# speed_truck.net
KiCad netlist of a schematic drawn in EasyEDA
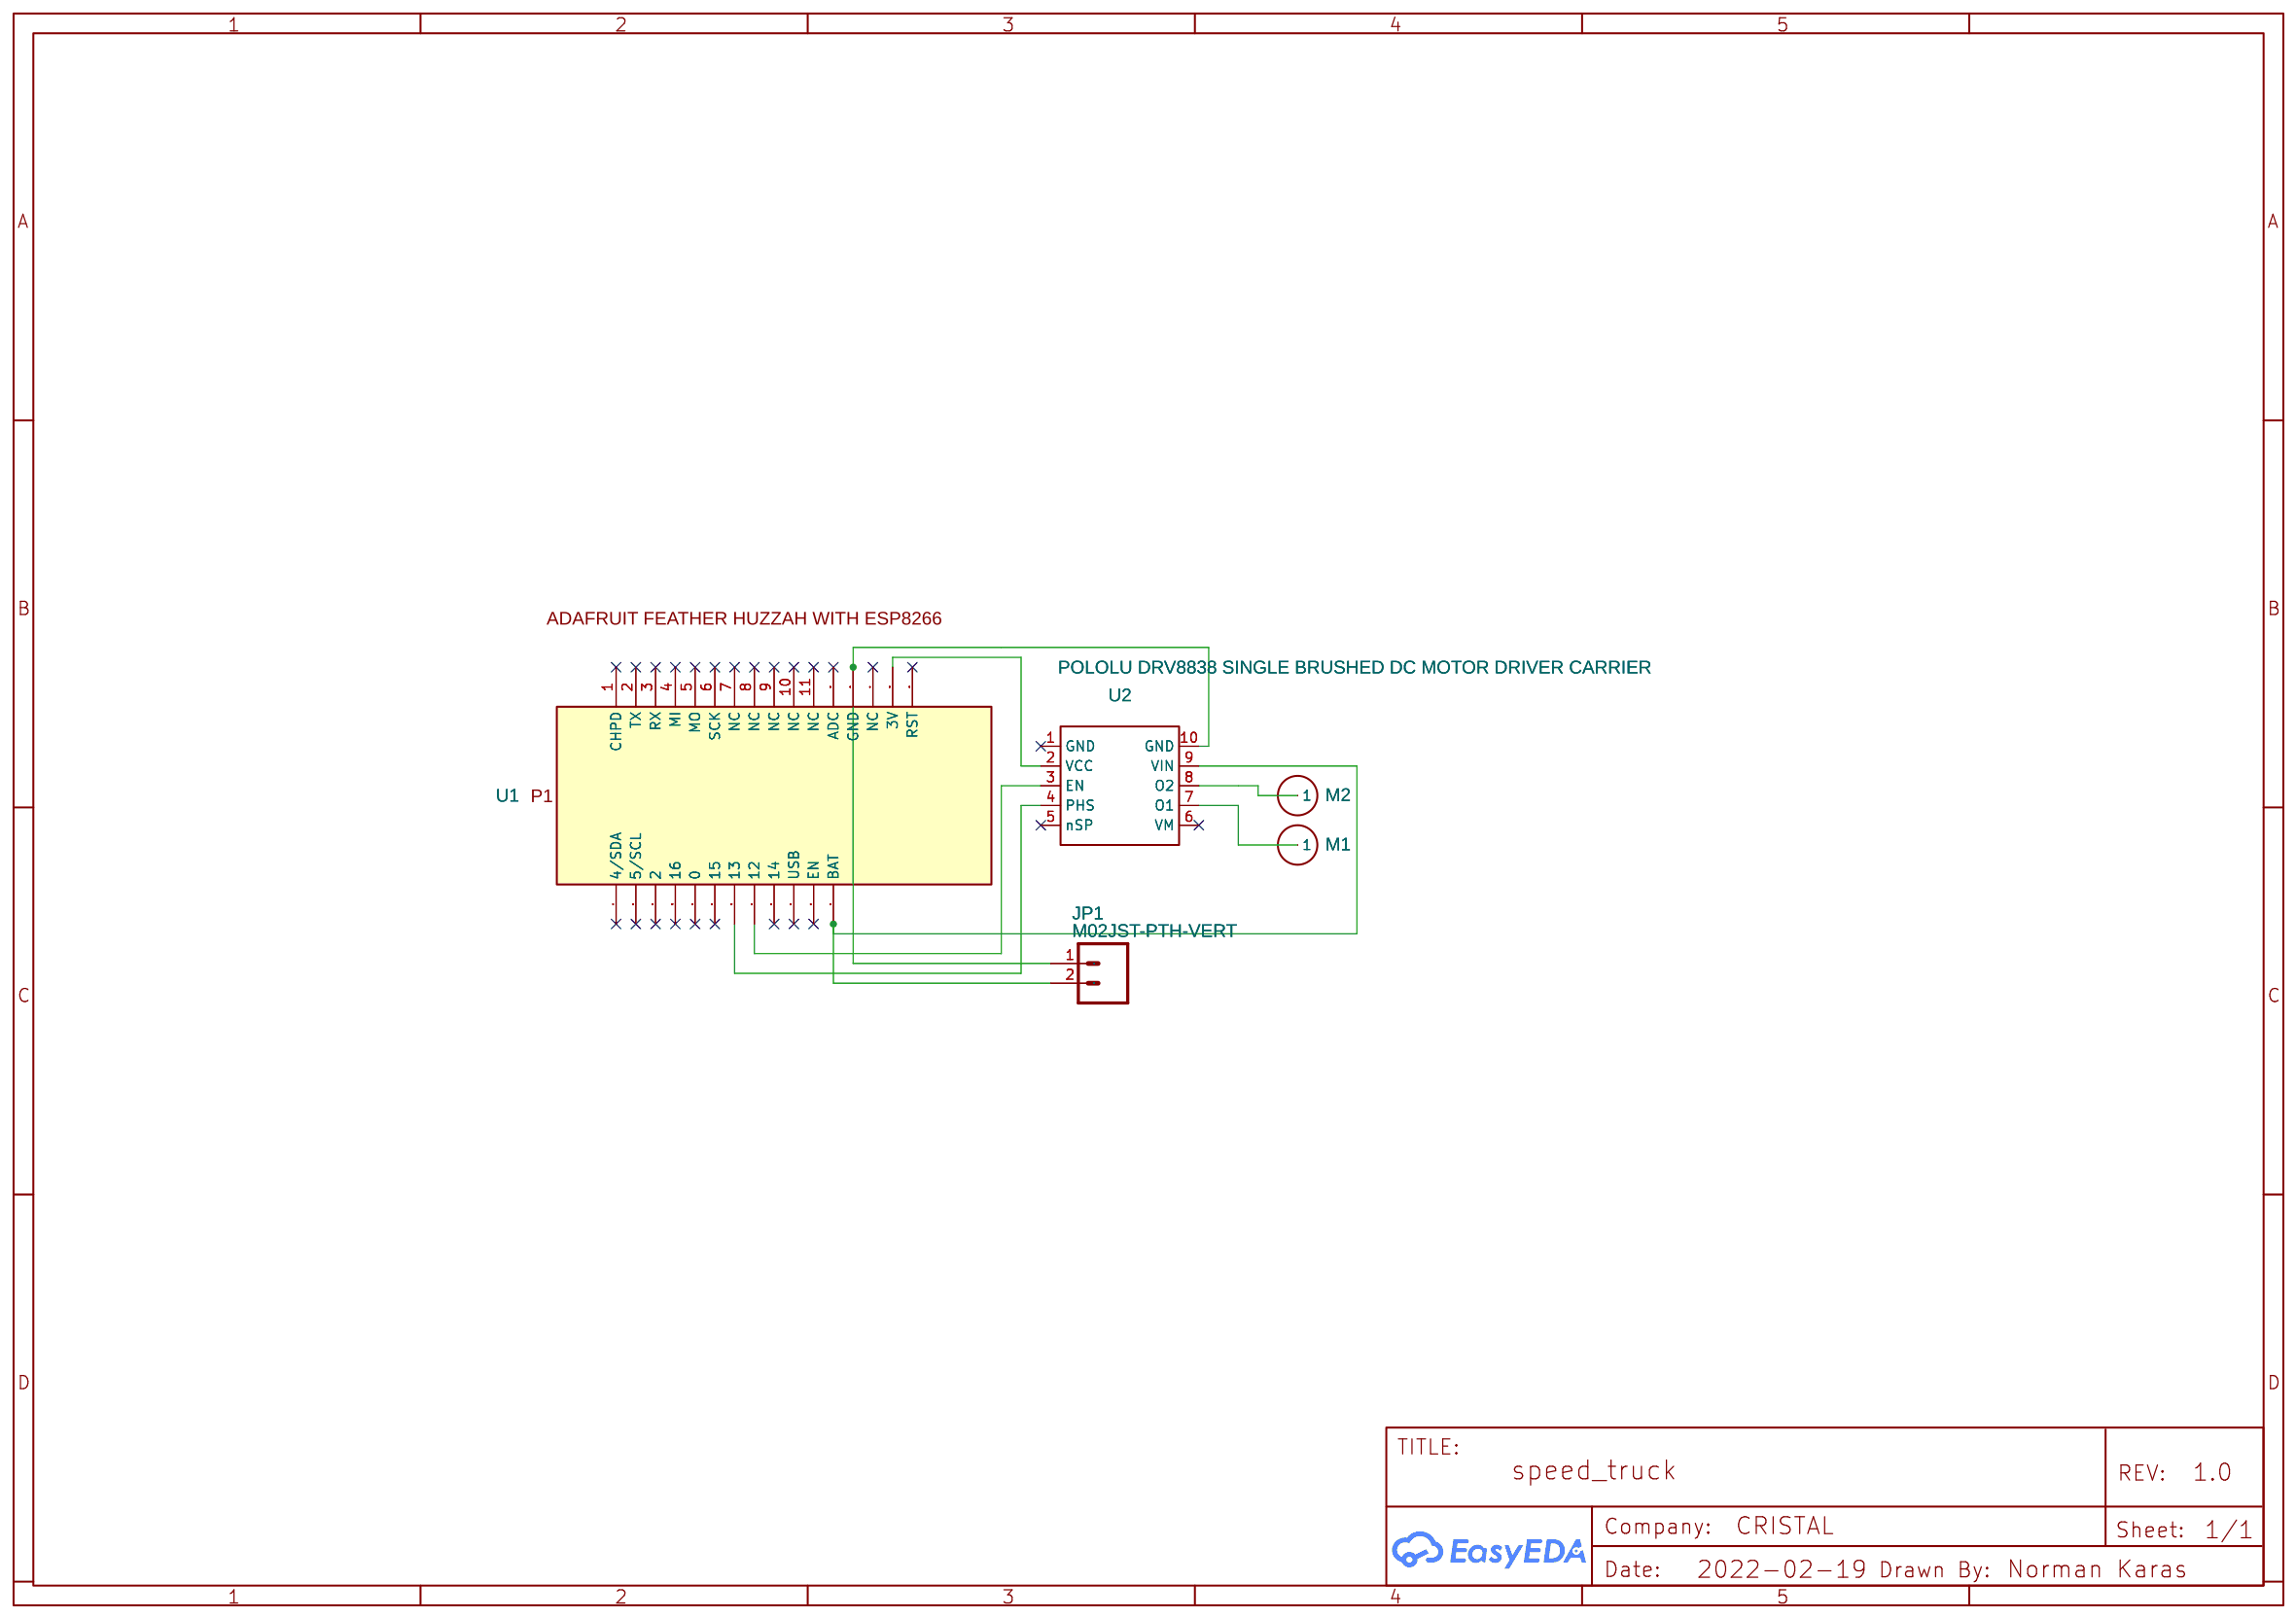
[diagram p0: schematic sheet]

(export (version "E")
  (design (tool "Eeschema 10.0.6"))
  (components
    (comp (ref "JP1") (value "M02JST-PTH-VERT") (libsource (lib "") (part "M02JST-PTH-VERT")))
    (comp (ref "M1")
      (value "Pad through hole 0.5mm hole 1mm pad")
      (libsource (lib "") (part "Pad through hole 0.5mm hole 1mm pad"))
    )
    (comp (ref "M2")
      (value "Pad through hole 0.5mm hole 1mm pad")
      (libsource (lib "") (part "Pad through hole 0.5mm hole 1mm pad"))
    )
    (comp (ref "U1")
      (value "Adafruit Huzzah ESP8266 - K5MAP")
      (libsource (lib "") (part "Adafruit Huzzah ESP8266 - K5MAP"))
    )
    (comp (ref "U2")
      (value "POLOLU DRV8838 SINGLE BRUSHED DC MOTOR DRIVER CARRIER")
      (fields (field (name "BOM_Manufacturer Part") "https://www.pololu.com/product/2990"))
      (libsource (lib "") (part "POLOLU DRV8838 SINGLE BRUSHED DC MOTOR DRIVER CARRIER"))
    )
  )
  (nets
    (net (code "1") (name "Net-(U1-3V)") (class "Default")
      (node (ref "U1") (pin "15") (pinfunction "3V_15") (pintype "unspecified"))
      (node (ref "U2") (pin "2") (pinfunction "VCC_2") (pintype "unspecified"))
    )
    (net (code "2") (name "Net-(U1-12)") (class "Default")
      (node (ref "U1") (pin "24") (pinfunction "12_24") (pintype "unspecified"))
      (node (ref "U2") (pin "3") (pinfunction "EN_3") (pintype "unspecified"))
    )
    (net (code "3") (name "Net-(U1-13)") (class "Default")
      (node (ref "U1") (pin "23") (pinfunction "13_23") (pintype "unspecified"))
      (node (ref "U2") (pin "4") (pinfunction "PHS_4") (pintype "unspecified"))
    )
    (net (code "4") (name "Net-(U1-BAT)") (class "Default")
      (node (ref "JP1") (pin "2") (pinfunction "2_2") (pintype "bidirectional"))
      (node (ref "U1") (pin "28") (pinfunction "BAT_28") (pintype "unspecified"))
      (node (ref "U2") (pin "9") (pinfunction "VIN_9") (pintype "unspecified"))
    )
    (net (code "5") (name "Net-(U1-GND)") (class "Default")
      (node (ref "JP1") (pin "1") (pinfunction "1_1") (pintype "bidirectional"))
      (node (ref "U1") (pin "13") (pinfunction "GND_13") (pintype "unspecified"))
      (node (ref "U2") (pin "10") (pinfunction "GND_10") (pintype "unspecified"))
    )
    (net (code "6") (name "Net-(U2-O1)") (class "Default")
      (node (ref "M1") (pin "1") (pinfunction "1_1") (pintype "unspecified"))
      (node (ref "U2") (pin "7") (pinfunction "O1_7") (pintype "unspecified"))
    )
    (net (code "7") (name "Net-(U2-O2)") (class "Default")
      (node (ref "M2") (pin "1") (pinfunction "1_1") (pintype "unspecified"))
      (node (ref "U2") (pin "8") (pinfunction "O2_8") (pintype "unspecified"))
    )
    (net (code "8") (name "unconnected-(U1-0-Pad21)") (class "Default")
      (node (ref "U1") (pin "21") (pinfunction "0_21") (pintype "unspecified+no_connect"))
    )
    (net (code "9") (name "unconnected-(U1-2-Pad19)") (class "Default")
      (node (ref "U1") (pin "19") (pinfunction "2_19") (pintype "unspecified+no_connect"))
    )
    (net (code "10") (name "unconnected-(U1-4{slash}SDA-Pad17)") (class "Default")
      (node (ref "U1") (pin "17") (pinfunction "4/SDA_17") (pintype "unspecified+no_connect"))
    )
    (net (code "11") (name "unconnected-(U1-5{slash}SCL-Pad18)") (class "Default")
      (node (ref "U1") (pin "18") (pinfunction "5/SCL_18") (pintype "unspecified+no_connect"))
    )
    (net (code "12") (name "unconnected-(U1-14-Pad25)") (class "Default")
      (node (ref "U1") (pin "25") (pinfunction "14_25") (pintype "unspecified+no_connect"))
    )
    (net (code "13") (name "unconnected-(U1-15-Pad22)") (class "Default")
      (node (ref "U1") (pin "22") (pinfunction "15_22") (pintype "unspecified+no_connect"))
    )
    (net (code "14") (name "unconnected-(U1-16-Pad20)") (class "Default")
      (node (ref "U1") (pin "20") (pinfunction "16_20") (pintype "unspecified+no_connect"))
    )
    (net (code "15") (name "unconnected-(U1-ADC-Pad12)") (class "Default")
      (node (ref "U1") (pin "12") (pinfunction "ADC_12") (pintype "unspecified+no_connect"))
    )
    (net (code "16") (name "unconnected-(U1-CHPD-Pad1)") (class "Default")
      (node (ref "U1") (pin "1") (pinfunction "CHPD_1") (pintype "unspecified+no_connect"))
    )
    (net (code "17") (name "unconnected-(U1-EN-Pad27)") (class "Default")
      (node (ref "U1") (pin "27") (pinfunction "EN_27") (pintype "unspecified+no_connect"))
    )
    (net (code "18") (name "unconnected-(U1-MI-Pad4)") (class "Default")
      (node (ref "U1") (pin "4") (pinfunction "MI_4") (pintype "unspecified+no_connect"))
    )
    (net (code "19") (name "unconnected-(U1-MO-Pad5)") (class "Default")
      (node (ref "U1") (pin "5") (pinfunction "MO_5") (pintype "unspecified+no_connect"))
    )
    (net (code "20") (name "unconnected-(U1-NC-Pad7)") (class "Default")
      (node (ref "U1") (pin "7") (pinfunction "NC_7") (pintype "unspecified+no_connect"))
    )
    (net (code "21") (name "unconnected-(U1-NC-Pad8)") (class "Default")
      (node (ref "U1") (pin "8") (pinfunction "NC_8") (pintype "unspecified+no_connect"))
    )
    (net (code "22") (name "unconnected-(U1-NC-Pad9)") (class "Default")
      (node (ref "U1") (pin "9") (pinfunction "NC_9") (pintype "unspecified+no_connect"))
    )
    (net (code "23") (name "unconnected-(U1-NC-Pad10)") (class "Default")
      (node (ref "U1") (pin "10") (pinfunction "NC_10") (pintype "unspecified+no_connect"))
    )
    (net (code "24") (name "unconnected-(U1-NC-Pad11)") (class "Default")
      (node (ref "U1") (pin "11") (pinfunction "NC_11") (pintype "unspecified+no_connect"))
    )
    (net (code "25") (name "unconnected-(U1-NC-Pad14)") (class "Default")
      (node (ref "U1") (pin "14") (pinfunction "NC_14") (pintype "unspecified+no_connect"))
    )
    (net (code "26") (name "unconnected-(U1-RST-Pad16)") (class "Default")
      (node (ref "U1") (pin "16") (pinfunction "RST_16") (pintype "unspecified+no_connect"))
    )
    (net (code "27") (name "unconnected-(U1-RX-Pad3)") (class "Default")
      (node (ref "U1") (pin "3") (pinfunction "RX_3") (pintype "unspecified+no_connect"))
    )
    (net (code "28") (name "unconnected-(U1-SCK-Pad6)") (class "Default")
      (node (ref "U1") (pin "6") (pinfunction "SCK_6") (pintype "unspecified+no_connect"))
    )
    (net (code "29") (name "unconnected-(U1-TX-Pad2)") (class "Default")
      (node (ref "U1") (pin "2") (pinfunction "TX_2") (pintype "unspecified+no_connect"))
    )
    (net (code "30") (name "unconnected-(U1-USB-Pad26)") (class "Default")
      (node (ref "U1") (pin "26") (pinfunction "USB_26") (pintype "unspecified+no_connect"))
    )
    (net (code "31") (name "unconnected-(U2-GND-Pad1)") (class "Default")
      (node (ref "U2") (pin "1") (pinfunction "GND_1") (pintype "unspecified+no_connect"))
    )
    (net (code "32") (name "unconnected-(U2-VM-Pad6)") (class "Default")
      (node (ref "U2") (pin "6") (pinfunction "VM_6") (pintype "unspecified+no_connect"))
    )
    (net (code "33") (name "unconnected-(U2-nSP-Pad5)") (class "Default")
      (node (ref "U2") (pin "5") (pinfunction "nSP_5") (pintype "unspecified+no_connect"))
    )
  )
)
